# schematic_easyeda.net
KiCad netlist of a schematic drawn in EasyEDA
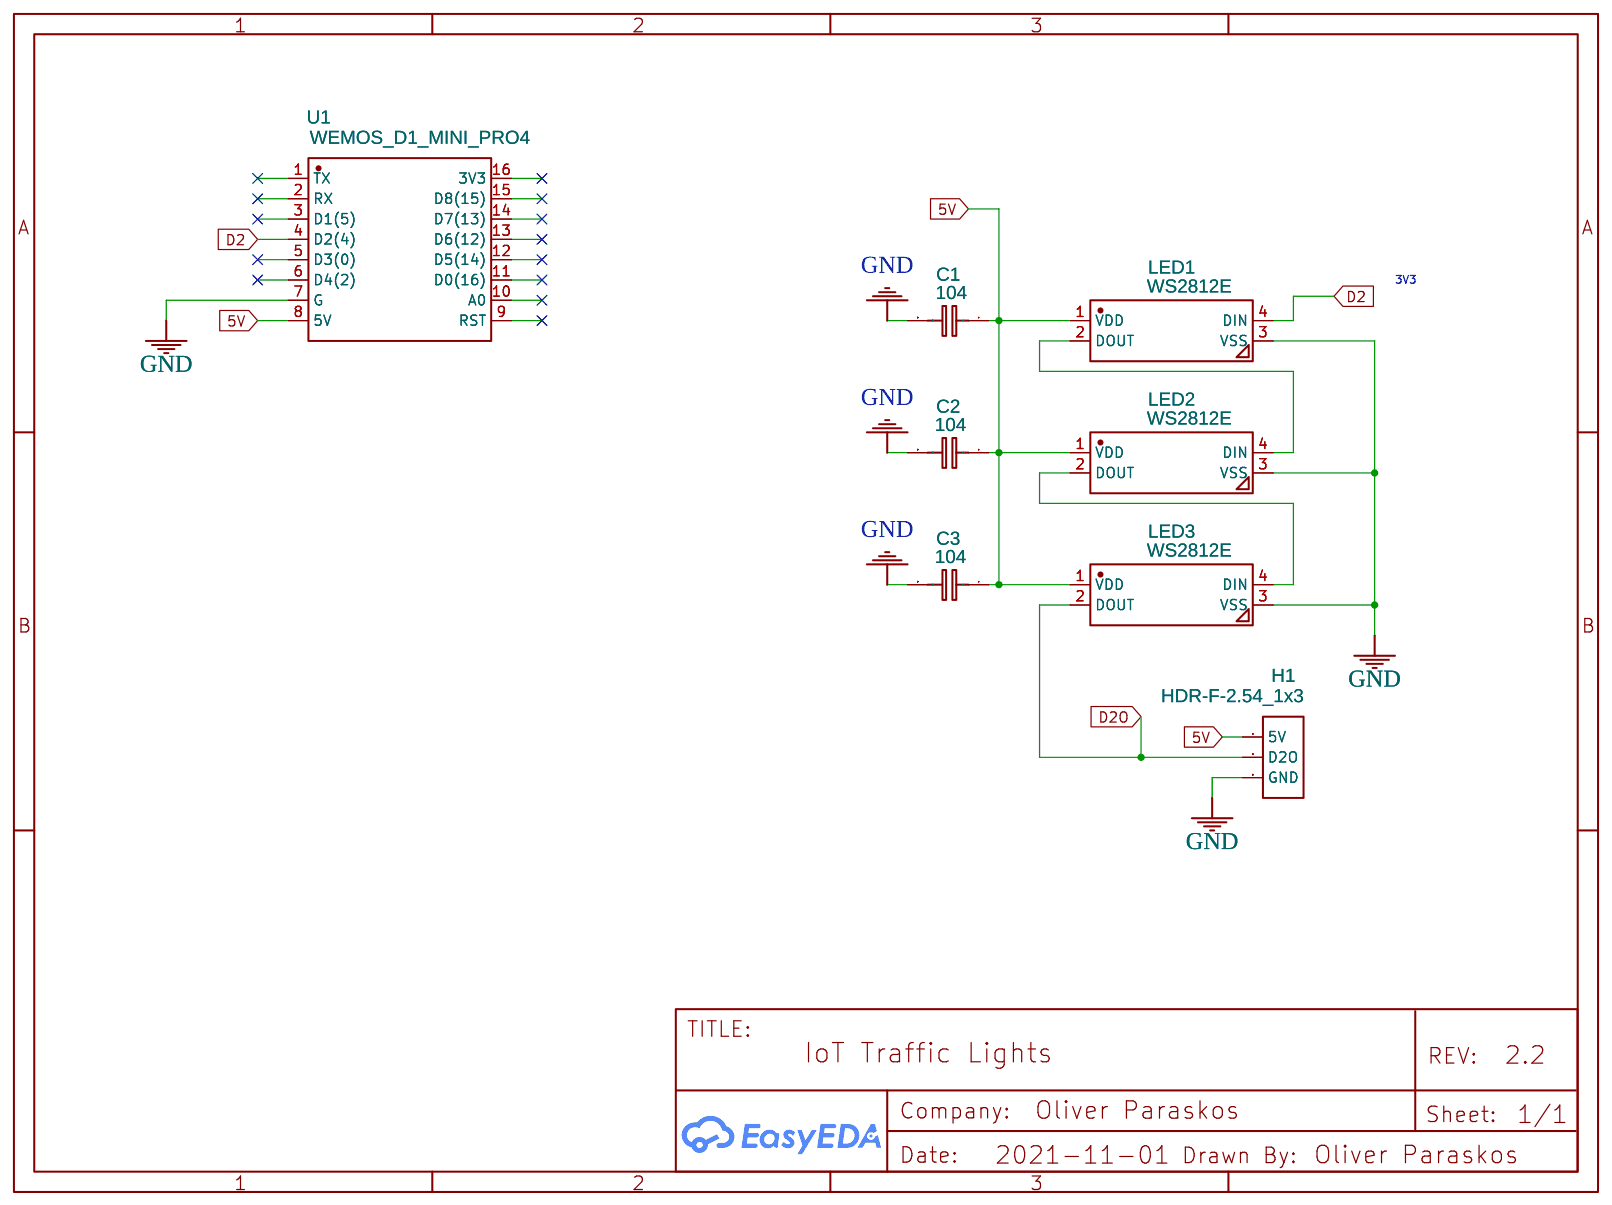
[diagram p0: schematic sheet]

(export (version "E")
  (design (tool "Eeschema 10.0.6"))
  (components
    (comp (ref "C1") (value "104") (libsource (lib "") (part "C_1206_EU")))
    (comp (ref "C2") (value "104") (libsource (lib "") (part "C_1206_EU")))
    (comp (ref "C3") (value "104") (libsource (lib "") (part "C_1206_EU")))
    (comp (ref "H1")
      (value "HDR-F-2.54_1x3")
      (fields (field (name "BOM_Supplier Part") "C146690"))
      (libsource (lib "") (part "HDR-F-2.54_1x3"))
    )
    (comp (ref "LED1")
      (value "WS2812E")
      (fields (field (name "BOM_Supplier Part") "C139127"))
      (libsource (lib "") (part "WS2812E"))
    )
    (comp (ref "LED2")
      (value "WS2812E")
      (fields (field (name "BOM_Supplier Part") "C139127"))
      (libsource (lib "") (part "WS2812E"))
    )
    (comp (ref "LED3")
      (value "WS2812E")
      (fields (field (name "BOM_Supplier Part") "C139127"))
      (libsource (lib "") (part "WS2812E"))
    )
    (comp (ref "U1")
      (value "WEMOS_D1_MINI_PRO4")
      (fields
        (field (name "BOM_Manufacturer Part") "Wemos_D1_mini_Pro4")
        (field (name "BOM_Supplier Part") "C2837266")
      )
      (libsource (lib "") (part "WEMOS_D1_MINI_PRO4"))
    )
  )
  (nets
    (net (code "1") (name "5V") (class "Default")
      (node (ref "C1") (pin "1") (pinfunction "1_1") (pintype "unspecified"))
      (node (ref "C2") (pin "1") (pinfunction "1_1") (pintype "unspecified"))
      (node (ref "C3") (pin "1") (pinfunction "1_1") (pintype "unspecified"))
      (node (ref "H1") (pin "1") (pinfunction "5V_1") (pintype "input"))
      (node (ref "LED1") (pin "1") (pinfunction "VDD_1") (pintype "unspecified"))
      (node (ref "LED2") (pin "1") (pinfunction "VDD_1") (pintype "unspecified"))
      (node (ref "LED3") (pin "1") (pinfunction "VDD_1") (pintype "unspecified"))
      (node (ref "U1") (pin "8") (pinfunction "5V_8") (pintype "unspecified"))
    )
    (net (code "2") (name "D2") (class "Default")
      (node (ref "LED1") (pin "4") (pinfunction "DIN_4") (pintype "unspecified"))
      (node (ref "U1") (pin "4") (pinfunction "D2(4)_4") (pintype "unspecified"))
    )
    (net (code "3") (name "D2O") (class "Default")
      (node (ref "H1") (pin "2") (pinfunction "D2O_2") (pintype "input"))
      (node (ref "LED3") (pin "2") (pinfunction "DOUT_2") (pintype "unspecified"))
    )
    (net (code "4") (name "GND") (class "Default")
      (node (ref "C1") (pin "2") (pinfunction "2_2") (pintype "unspecified"))
      (node (ref "C2") (pin "2") (pinfunction "2_2") (pintype "unspecified"))
      (node (ref "C3") (pin "2") (pinfunction "2_2") (pintype "unspecified"))
      (node (ref "H1") (pin "3") (pinfunction "GND_3") (pintype "input"))
      (node (ref "LED1") (pin "3") (pinfunction "VSS_3") (pintype "unspecified"))
      (node (ref "LED2") (pin "3") (pinfunction "VSS_3") (pintype "unspecified"))
      (node (ref "LED3") (pin "3") (pinfunction "VSS_3") (pintype "unspecified"))
      (node (ref "U1") (pin "7") (pinfunction "G_7") (pintype "unspecified"))
    )
    (net (code "5") (name "Net-(LED1-DOUT)") (class "Default")
      (node (ref "LED1") (pin "2") (pinfunction "DOUT_2") (pintype "unspecified"))
      (node (ref "LED2") (pin "4") (pinfunction "DIN_4") (pintype "unspecified"))
    )
    (net (code "6") (name "Net-(LED2-DOUT)") (class "Default")
      (node (ref "LED2") (pin "2") (pinfunction "DOUT_2") (pintype "unspecified"))
      (node (ref "LED3") (pin "4") (pinfunction "DIN_4") (pintype "unspecified"))
    )
    (net (code "7") (name "unconnected-(U1-3V3-Pad16)") (class "Default")
      (node (ref "U1") (pin "16") (pinfunction "3V3_16") (pintype "unspecified+no_connect"))
    )
    (net (code "8") (name "unconnected-(U1-A0-Pad10)") (class "Default")
      (node (ref "U1") (pin "10") (pinfunction "A0_10") (pintype "unspecified+no_connect"))
    )
    (net (code "9") (name "unconnected-(U1-D0(16)-Pad11)") (class "Default")
      (node (ref "U1") (pin "11") (pinfunction "D0(16)_11") (pintype "unspecified+no_connect"))
    )
    (net (code "10") (name "unconnected-(U1-D1(5)-Pad3)") (class "Default")
      (node (ref "U1") (pin "3") (pinfunction "D1(5)_3") (pintype "unspecified+no_connect"))
    )
    (net (code "11") (name "unconnected-(U1-D3(0)-Pad5)") (class "Default")
      (node (ref "U1") (pin "5") (pinfunction "D3(0)_5") (pintype "unspecified+no_connect"))
    )
    (net (code "12") (name "unconnected-(U1-D4(2)-Pad6)") (class "Default")
      (node (ref "U1") (pin "6") (pinfunction "D4(2)_6") (pintype "unspecified+no_connect"))
    )
    (net (code "13") (name "unconnected-(U1-D5(14)-Pad12)") (class "Default")
      (node (ref "U1") (pin "12") (pinfunction "D5(14)_12") (pintype "unspecified+no_connect"))
    )
    (net (code "14") (name "unconnected-(U1-D6(12)-Pad13)") (class "Default")
      (node (ref "U1") (pin "13") (pinfunction "D6(12)_13") (pintype "unspecified+no_connect"))
    )
    (net (code "15") (name "unconnected-(U1-D7(13)-Pad14)") (class "Default")
      (node (ref "U1") (pin "14") (pinfunction "D7(13)_14") (pintype "unspecified+no_connect"))
    )
    (net (code "16") (name "unconnected-(U1-D8(15)-Pad15)") (class "Default")
      (node (ref "U1") (pin "15") (pinfunction "D8(15)_15") (pintype "unspecified+no_connect"))
    )
    (net (code "17") (name "unconnected-(U1-RST-Pad9)") (class "Default")
      (node (ref "U1") (pin "9") (pinfunction "RST_9") (pintype "unspecified+no_connect"))
    )
    (net (code "18") (name "unconnected-(U1-RX-Pad2)") (class "Default")
      (node (ref "U1") (pin "2") (pinfunction "RX_2") (pintype "unspecified+no_connect"))
    )
    (net (code "19") (name "unconnected-(U1-TX-Pad1)") (class "Default")
      (node (ref "U1") (pin "1") (pinfunction "TX_1") (pintype "unspecified+no_connect"))
    )
  )
)
